# motor_driver_shield.net
KiCad netlist of a schematic drawn in EAGLE
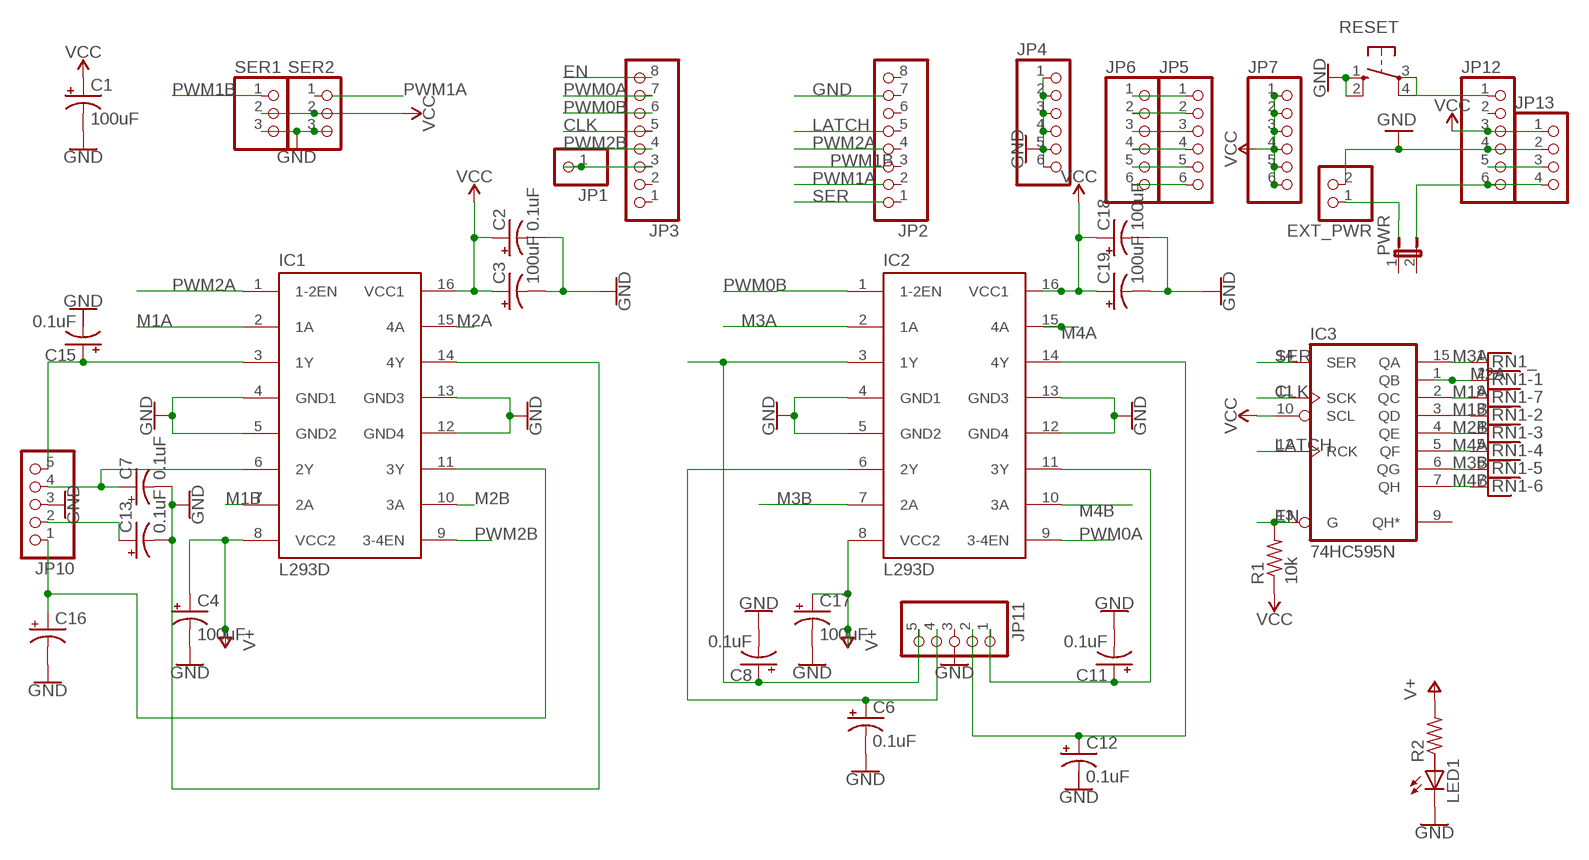
[diagram p0: schematic, sheet 1]

(export (version "E")
  (design (tool "Eeschema 10.0.6"))
  (components
    (comp (ref "C1")
      (value "100uF")
      (footprint "eagle-import:B45181A")
      (libsource (lib "eagle-import") (part "CPOL-USB45181A"))
    )
    (comp (ref "C2")
      (value "0.1uF")
      (footprint "eagle-import:B45181A")
      (libsource (lib "eagle-import") (part "CPOL-USB45181A"))
    )
    (comp (ref "C3")
      (value "100uF")
      (footprint "eagle-import:B45181A")
      (libsource (lib "eagle-import") (part "CPOL-USB45181A"))
    )
    (comp (ref "C4")
      (value "100uF")
      (footprint "eagle-import:B45181A")
      (libsource (lib "eagle-import") (part "CPOL-USB45181A"))
    )
    (comp (ref "C6")
      (value "0.1uF")
      (footprint "eagle-import:B45181A")
      (libsource (lib "eagle-import") (part "CPOL-USB45181A"))
    )
    (comp (ref "C7")
      (value "0.1uF")
      (footprint "eagle-import:B45181A")
      (libsource (lib "eagle-import") (part "CPOL-USB45181A"))
    )
    (comp (ref "C8")
      (value "0.1uF")
      (footprint "eagle-import:B45181A")
      (libsource (lib "eagle-import") (part "CPOL-USB45181A"))
    )
    (comp (ref "C11")
      (value "0.1uF")
      (footprint "eagle-import:B45181A")
      (libsource (lib "eagle-import") (part "CPOL-USB45181A"))
    )
    (comp (ref "C12")
      (value "0.1uF")
      (footprint "eagle-import:B45181A")
      (libsource (lib "eagle-import") (part "CPOL-USB45181A"))
    )
    (comp (ref "C13")
      (value "0.1uF")
      (footprint "eagle-import:B45181A")
      (libsource (lib "eagle-import") (part "CPOL-USB45181A"))
    )
    (comp (ref "C15")
      (value "0.1uF")
      (footprint "eagle-import:B45181A")
      (libsource (lib "eagle-import") (part "CPOL-USB45181A"))
    )
    (comp (ref "C16")
      (value "CPOL-USB45181A")
      (footprint "eagle-import:B45181A")
      (libsource (lib "eagle-import") (part "CPOL-USB45181A"))
    )
    (comp (ref "C17")
      (value "100uF")
      (footprint "eagle-import:B45181A")
      (libsource (lib "eagle-import") (part "CPOL-USB45181A"))
    )
    (comp (ref "C18")
      (value "100uF")
      (footprint "eagle-import:B45181A")
      (libsource (lib "eagle-import") (part "CPOL-USB45181A"))
    )
    (comp (ref "C19")
      (value "100uF")
      (footprint "eagle-import:B45181A")
      (libsource (lib "eagle-import") (part "CPOL-USB45181A"))
    )
    (comp (ref "EXT_PWR")
      (value "PINHD-1X2")
      (footprint "eagle-import:1X02")
      (libsource (lib "eagle-import") (part "PINHD-1X2"))
    )
    (comp (ref "IC1")
      (value "L293D")
      (footprint "eagle-import:DIL16")
      (libsource (lib "eagle-import") (part "L293D"))
    )
    (comp (ref "IC2")
      (value "L293D")
      (footprint "eagle-import:DIL16")
      (libsource (lib "eagle-import") (part "L293D"))
    )
    (comp (ref "IC3")
      (value "74HC595N")
      (footprint "eagle-import:DIL16")
      (libsource (lib "eagle-import") (part "74595NHC"))
    )
    (comp (ref "JP1")
      (value "PINHD-1X1")
      (footprint "eagle-import:1X01")
      (libsource (lib "eagle-import") (part "PINHD-1X1"))
    )
    (comp (ref "JP2")
      (value "PINHD-1X8-3.5MM")
      (footprint "eagle-import:1X08-3.5MM")
      (libsource (lib "eagle-import") (part "PINHD-1X8-3.5MM"))
    )
    (comp (ref "JP3")
      (value "PINHD-1X8-3.5MM")
      (footprint "eagle-import:1X08-3.5MM")
      (libsource (lib "eagle-import") (part "PINHD-1X8-3.5MM"))
    )
    (comp (ref "JP4")
      (value "PINHD-1X6-3.5MM")
      (footprint "eagle-import:1X06-3.5MM")
      (libsource (lib "eagle-import") (part "PINHD-1X6-3.5MM"))
    )
    (comp (ref "JP5")
      (value "PINHD-1X6-3.5MM")
      (footprint "eagle-import:1X06-3.5MM")
      (libsource (lib "eagle-import") (part "PINHD-1X6-3.5MM"))
    )
    (comp (ref "JP6")
      (value "PINHD-1X6-3.5MM")
      (footprint "eagle-import:1X06-3.5MM")
      (libsource (lib "eagle-import") (part "PINHD-1X6-3.5MM"))
    )
    (comp (ref "JP7")
      (value "PINHD-1X6-3.5MM")
      (footprint "eagle-import:1X06-3.5MM")
      (libsource (lib "eagle-import") (part "PINHD-1X6-3.5MM"))
    )
    (comp (ref "JP10")
      (value "PINHD-1X5")
      (footprint "eagle-import:1X05")
      (libsource (lib "eagle-import") (part "PINHD-1X5"))
    )
    (comp (ref "JP11")
      (value "PINHD-1X5")
      (footprint "eagle-import:1X05")
      (libsource (lib "eagle-import") (part "PINHD-1X5"))
    )
    (comp (ref "JP12")
      (value "PINHD-1X6-3.5MM")
      (footprint "eagle-import:1X06-3.5MM")
      (libsource (lib "eagle-import") (part "PINHD-1X6-3.5MM"))
    )
    (comp (ref "JP13")
      (value "PINHD-1X4")
      (footprint "eagle-import:1X04")
      (libsource (lib "eagle-import") (part "PINHD-1X4"))
    )
    (comp (ref "LED1")
      (value "LED5MM")
      (footprint "eagle-import:LED5MM")
      (libsource (lib "eagle-import") (part "LED5MM"))
    )
    (comp (ref "PWR")
      (value "JP1E")
      (footprint "eagle-import:JP1")
      (libsource (lib "eagle-import") (part "JP1E"))
    )
    (comp (ref "R1")
      (value "10k")
      (footprint "eagle-import:0204V")
      (libsource (lib "eagle-import") (part "R-US_0204/2V"))
    )
    (comp (ref "R2")
      (value "R-US_0204/2V")
      (footprint "eagle-import:0204V")
      (libsource (lib "eagle-import") (part "R-US_0204/2V"))
    )
    (comp (ref "RESET")
      (value "40-XX")
      (footprint "eagle-import:B3F-40XX")
      (fields (field (name "MF") "OMRON COMPONENTS USA") (field (name "MPN") "B3F-4000"))
      (libsource (lib "eagle-import") (part "40-XX"))
    )
    (comp (ref "RN1")
      (value "RNX7")
      (footprint "eagle-import:RN-8")
      (libsource (lib "eagle-import") (part "RNX7"))
    )
    (comp (ref "SER1")
      (value "PINHD-1X3")
      (footprint "eagle-import:1X03")
      (libsource (lib "eagle-import") (part "PINHD-1X3"))
    )
    (comp (ref "SER2")
      (value "PINHD-1X3")
      (footprint "eagle-import:1X03")
      (libsource (lib "eagle-import") (part "PINHD-1X3"))
    )
  )
  (nets
    (net (code "1") (name "/CLK") (class "Default")
      (node (ref "IC3") (pin "11") (pinfunction "SCK_11") (pintype "input"))
      (node (ref "JP3") (pin "5") (pinfunction "5_5") (pintype "passive"))
    )
    (net (code "2") (name "/EN") (class "Default")
      (node (ref "IC3") (pin "13") (pinfunction "G_13") (pintype "input"))
      (node (ref "JP3") (pin "8") (pinfunction "8_8") (pintype "passive"))
      (node (ref "R1") (pin "2") (pinfunction "2_2") (pintype "passive"))
    )
    (net (code "3") (name "/LATCH") (class "Default")
      (node (ref "IC3") (pin "12") (pinfunction "RCK_12") (pintype "input"))
    )
    (net (code "4") (name "/M1A") (class "Default")
      (node (ref "IC1") (pin "2") (pinfunction "1A_2") (pintype "input"))
      (node (ref "IC3") (pin "2") (pinfunction "QC_2") (pintype "tri_state"))
      (node (ref "RN1") (pin "8") (pinfunction "1_8") (pintype "passive"))
    )
    (net (code "5") (name "/M1B") (class "Default")
      (node (ref "IC1") (pin "7") (pinfunction "2A_7") (pintype "input"))
      (node (ref "IC3") (pin "3") (pinfunction "QD_3") (pintype "tri_state"))
      (node (ref "RN1") (pin "3") (pinfunction "1_3") (pintype "passive"))
    )
    (net (code "6") (name "/M2A") (class "Default")
      (node (ref "IC1") (pin "15") (pinfunction "4A_15") (pintype "input"))
      (node (ref "IC3") (pin "1") (pinfunction "QB_1") (pintype "tri_state"))
      (node (ref "RN1") (pin "2") (pinfunction "1_2") (pintype "passive"))
    )
    (net (code "7") (name "/M2B") (class "Default")
      (node (ref "IC1") (pin "10") (pinfunction "3A_10") (pintype "input"))
      (node (ref "IC3") (pin "4") (pinfunction "QE_4") (pintype "tri_state"))
      (node (ref "RN1") (pin "4") (pinfunction "1_4") (pintype "passive"))
    )
    (net (code "8") (name "/M3A") (class "Default")
      (node (ref "IC2") (pin "2") (pinfunction "1A_2") (pintype "input"))
      (node (ref "IC3") (pin "15") (pinfunction "QA_15") (pintype "tri_state"))
      (node (ref "RN1") (pin "1") (pinfunction "1_1") (pintype "passive"))
    )
    (net (code "9") (name "/M3B") (class "Default")
      (node (ref "IC2") (pin "7") (pinfunction "2A_7") (pintype "input"))
      (node (ref "IC3") (pin "6") (pinfunction "QG_6") (pintype "tri_state"))
      (node (ref "RN1") (pin "6") (pinfunction "1_6") (pintype "passive"))
    )
    (net (code "10") (name "/M4A") (class "Default")
      (node (ref "IC2") (pin "15") (pinfunction "4A_15") (pintype "input"))
      (node (ref "IC3") (pin "5") (pinfunction "QF_5") (pintype "tri_state"))
      (node (ref "RN1") (pin "5") (pinfunction "1_5") (pintype "passive"))
    )
    (net (code "11") (name "/M4B") (class "Default")
      (node (ref "IC2") (pin "10") (pinfunction "3A_10") (pintype "input"))
      (node (ref "IC3") (pin "7") (pinfunction "QH_7") (pintype "tri_state"))
      (node (ref "RN1") (pin "7") (pinfunction "1_7") (pintype "passive"))
    )
    (net (code "12") (name "/PWM0A") (class "Default")
      (node (ref "IC2") (pin "9") (pinfunction "3-4EN_9") (pintype "input"))
      (node (ref "JP3") (pin "7") (pinfunction "7_7") (pintype "passive"))
    )
    (net (code "13") (name "/PWM0B") (class "Default")
      (node (ref "IC2") (pin "1") (pinfunction "1-2EN_1") (pintype "input"))
      (node (ref "JP3") (pin "6") (pinfunction "6_6") (pintype "passive"))
    )
    (net (code "15") (name "/PWM1B") (class "Default")
      (node (ref "SER1") (pin "1") (pinfunction "1_1") (pintype "passive"))
    )
    (net (code "16") (name "/PWM2A") (class "Default")
      (node (ref "IC1") (pin "1") (pinfunction "1-2EN_1") (pintype "input"))
    )
    (net (code "17") (name "/PWM2B") (class "Default")
      (node (ref "IC1") (pin "9") (pinfunction "3-4EN_9") (pintype "input"))
      (node (ref "JP3") (pin "4") (pinfunction "4_4") (pintype "passive"))
    )
    (net (code "18") (name "/SER") (class "Default")
      (node (ref "IC3") (pin "14") (pinfunction "SER_14") (pintype "input"))
    )
    (net (code "19") (name "GND") (class "Default")
      (node (ref "C1") (pin "-") (pinfunction "-_-") (pintype "passive"))
      (node (ref "C11") (pin "-") (pinfunction "-_-") (pintype "passive"))
      (node (ref "C13") (pin "-") (pinfunction "-_-") (pintype "passive"))
      (node (ref "C16") (pin "-") (pinfunction "-_-") (pintype "passive"))
      (node (ref "C17") (pin "-") (pinfunction "-_-") (pintype "passive"))
      (node (ref "C18") (pin "-") (pinfunction "-_-") (pintype "passive"))
      (node (ref "C19") (pin "-") (pinfunction "-_-") (pintype "passive"))
      (node (ref "C2") (pin "-") (pinfunction "-_-") (pintype "passive"))
      (node (ref "C3") (pin "-") (pinfunction "-_-") (pintype "passive"))
      (node (ref "C4") (pin "-") (pinfunction "-_-") (pintype "passive"))
      (node (ref "C6") (pin "-") (pinfunction "-_-") (pintype "passive"))
      (node (ref "C7") (pin "-") (pinfunction "-_-") (pintype "passive"))
      (node (ref "C8") (pin "-") (pinfunction "-_-") (pintype "passive"))
      (node (ref "EXT_PWR") (pin "2") (pinfunction "2_2") (pintype "passive"))
      (node (ref "IC1") (pin "12") (pinfunction "GND4_12") (pintype "power_in"))
      (node (ref "IC1") (pin "13") (pinfunction "GND3_13") (pintype "power_in"))
      (node (ref "IC1") (pin "14") (pinfunction "4Y_14") (pintype "output"))
      (node (ref "IC1") (pin "4") (pinfunction "GND1_4") (pintype "power_in"))
      (node (ref "IC1") (pin "5") (pinfunction "GND2_5") (pintype "power_in"))
      (node (ref "IC2") (pin "12") (pinfunction "GND4_12") (pintype "power_in"))
      (node (ref "IC2") (pin "13") (pinfunction "GND3_13") (pintype "power_in"))
      (node (ref "IC2") (pin "4") (pinfunction "GND1_4") (pintype "power_in"))
      (node (ref "IC2") (pin "5") (pinfunction "GND2_5") (pintype "power_in"))
      (node (ref "JP10") (pin "3") (pinfunction "3_3") (pintype "passive"))
      (node (ref "JP12") (pin "4") (pinfunction "4_4") (pintype "passive"))
      (node (ref "JP13") (pin "2") (pinfunction "2_2") (pintype "passive"))
      (node (ref "JP4") (pin "1") (pinfunction "1_1") (pintype "passive"))
      (node (ref "JP4") (pin "2") (pinfunction "2_2") (pintype "passive"))
      (node (ref "JP4") (pin "3") (pinfunction "3_3") (pintype "passive"))
      (node (ref "JP4") (pin "4") (pinfunction "4_4") (pintype "passive"))
      (node (ref "JP4") (pin "5") (pinfunction "5_5") (pintype "passive"))
      (node (ref "JP4") (pin "6") (pinfunction "6_6") (pintype "passive"))
      (node (ref "LED1") (pin "K") (pinfunction "C_K") (pintype "passive"))
      (node (ref "RESET") (pin "1") (pinfunction "S_1") (pintype "passive"))
      (node (ref "RESET") (pin "2") (pinfunction "S1_2") (pintype "passive"))
      (node (ref "SER1") (pin "3") (pinfunction "3_3") (pintype "passive"))
      (node (ref "SER2") (pin "3") (pinfunction "3_3") (pintype "passive"))
    )
    (net (code "20") (name "Net-(C13-Pad+)") (class "Default")
      (node (ref "C13") (pin "+") (pinfunction "+_+") (pintype "passive"))
      (node (ref "JP10") (pin "2") (pinfunction "2_2") (pintype "passive"))
    )
    (net (code "21") (name "Net-(IC1-1Y)") (class "Default")
      (node (ref "C15") (pin "+") (pinfunction "+_+") (pintype "passive"))
      (node (ref "IC1") (pin "3") (pinfunction "1Y_3") (pintype "output"))
      (node (ref "JP10") (pin "5") (pinfunction "5_5") (pintype "passive"))
    )
    (net (code "22") (name "Net-(IC1-2Y)") (class "Default")
      (node (ref "C7") (pin "+") (pinfunction "+_+") (pintype "passive"))
      (node (ref "IC1") (pin "6") (pinfunction "2Y_6") (pintype "output"))
      (node (ref "JP10") (pin "4") (pinfunction "4_4") (pintype "passive"))
    )
    (net (code "23") (name "Net-(IC1-3Y)") (class "Default")
      (node (ref "C16") (pin "+") (pinfunction "+_+") (pintype "passive"))
      (node (ref "IC1") (pin "11") (pinfunction "3Y_11") (pintype "output"))
      (node (ref "JP10") (pin "1") (pinfunction "1_1") (pintype "passive"))
    )
    (net (code "24") (name "Net-(IC2-1Y)") (class "Default")
      (node (ref "C8") (pin "+") (pinfunction "+_+") (pintype "passive"))
      (node (ref "IC2") (pin "3") (pinfunction "1Y_3") (pintype "output"))
      (node (ref "JP11") (pin "5") (pinfunction "5_5") (pintype "passive"))
    )
    (net (code "25") (name "Net-(IC2-2Y)") (class "Default")
      (node (ref "C6") (pin "+") (pinfunction "+_+") (pintype "passive"))
      (node (ref "IC2") (pin "6") (pinfunction "2Y_6") (pintype "output"))
      (node (ref "JP11") (pin "4") (pinfunction "4_4") (pintype "passive"))
    )
    (net (code "26") (name "Net-(IC2-3Y)") (class "Default")
      (node (ref "C11") (pin "+") (pinfunction "+_+") (pintype "passive"))
      (node (ref "IC2") (pin "11") (pinfunction "3Y_11") (pintype "output"))
      (node (ref "JP11") (pin "1") (pinfunction "1_1") (pintype "passive"))
    )
    (net (code "27") (name "Net-(IC2-4Y)") (class "Default")
      (node (ref "C12") (pin "+") (pinfunction "+_+") (pintype "passive"))
      (node (ref "IC2") (pin "14") (pinfunction "4Y_14") (pintype "output"))
      (node (ref "JP11") (pin "2") (pinfunction "2_2") (pintype "passive"))
    )
    (net (code "28") (name "Net-(JP1-Pad1)") (class "Default")
      (node (ref "JP1") (pin "1") (pinfunction "1_1") (pintype "passive"))
      (node (ref "JP3") (pin "3") (pinfunction "3_3") (pintype "passive"))
    )
    (net (code "29") (name "Net-(JP5-Pad1)") (class "Default")
      (node (ref "JP5") (pin "1") (pinfunction "1_1") (pintype "passive"))
      (node (ref "JP6") (pin "1") (pinfunction "1_1") (pintype "passive"))
    )
    (net (code "30") (name "Net-(JP5-Pad2)") (class "Default")
      (node (ref "JP5") (pin "2") (pinfunction "2_2") (pintype "passive"))
      (node (ref "JP6") (pin "2") (pinfunction "2_2") (pintype "passive"))
    )
    (net (code "31") (name "Net-(JP5-Pad3)") (class "Default")
      (node (ref "JP5") (pin "3") (pinfunction "3_3") (pintype "passive"))
      (node (ref "JP6") (pin "3") (pinfunction "3_3") (pintype "passive"))
    )
    (net (code "32") (name "Net-(JP5-Pad4)") (class "Default")
      (node (ref "JP5") (pin "4") (pinfunction "4_4") (pintype "passive"))
      (node (ref "JP6") (pin "4") (pinfunction "4_4") (pintype "passive"))
    )
    (net (code "33") (name "Net-(JP5-Pad5)") (class "Default")
      (node (ref "JP5") (pin "5") (pinfunction "5_5") (pintype "passive"))
      (node (ref "JP6") (pin "5") (pinfunction "5_5") (pintype "passive"))
    )
    (net (code "34") (name "Net-(JP5-Pad6)") (class "Default")
      (node (ref "JP5") (pin "6") (pinfunction "6_6") (pintype "passive"))
      (node (ref "JP6") (pin "6") (pinfunction "6_6") (pintype "passive"))
    )
    (net (code "35") (name "Net-(JP12-Pad5)") (class "Default")
      (node (ref "JP12") (pin "5") (pinfunction "5_5") (pintype "passive"))
      (node (ref "JP13") (pin "3") (pinfunction "3_3") (pintype "passive"))
    )
    (net (code "36") (name "Net-(JP12-Pad6)") (class "Default")
      (node (ref "JP12") (pin "6") (pinfunction "6_6") (pintype "passive"))
      (node (ref "JP13") (pin "4") (pinfunction "4_4") (pintype "passive"))
    )
    (net (code "37") (name "Net-(RESET-P)") (class "Default")
      (node (ref "JP12") (pin "1") (pinfunction "1_1") (pintype "passive"))
      (node (ref "RESET") (pin "3") (pinfunction "P_3") (pintype "passive"))
      (node (ref "RESET") (pin "4") (pinfunction "P1_4") (pintype "passive"))
    )
    (net (code "38") (name "V+") (class "Default")
      (node (ref "C17") (pin "+") (pinfunction "+_+") (pintype "passive"))
      (node (ref "C4") (pin "+") (pinfunction "+_+") (pintype "passive"))
      (node (ref "IC1") (pin "8") (pinfunction "VCC2_8") (pintype "power_in"))
      (node (ref "IC2") (pin "8") (pinfunction "VCC2_8") (pintype "power_in"))
      (node (ref "R2") (pin "2") (pinfunction "2_2") (pintype "passive"))
    )
    (net (code "39") (name "VCC") (class "Default")
      (node (ref "C1") (pin "+") (pinfunction "+_+") (pintype "passive"))
      (node (ref "C18") (pin "+") (pinfunction "+_+") (pintype "passive"))
      (node (ref "C19") (pin "+") (pinfunction "+_+") (pintype "passive"))
      (node (ref "C2") (pin "+") (pinfunction "+_+") (pintype "passive"))
      (node (ref "C3") (pin "+") (pinfunction "+_+") (pintype "passive"))
      (node (ref "IC1") (pin "16") (pinfunction "VCC1_16") (pintype "power_in"))
      (node (ref "IC2") (pin "16") (pinfunction "VCC1_16") (pintype "power_in"))
      (node (ref "IC3") (pin "10") (pinfunction "SCL_10") (pintype "input"))
      (node (ref "JP12") (pin "3") (pinfunction "3_3") (pintype "passive"))
      (node (ref "JP13") (pin "1") (pinfunction "1_1") (pintype "passive"))
      (node (ref "JP7") (pin "1") (pinfunction "1_1") (pintype "passive"))
      (node (ref "JP7") (pin "2") (pinfunction "2_2") (pintype "passive"))
      (node (ref "JP7") (pin "3") (pinfunction "3_3") (pintype "passive"))
      (node (ref "JP7") (pin "4") (pinfunction "4_4") (pintype "passive"))
      (node (ref "JP7") (pin "5") (pinfunction "5_5") (pintype "passive"))
      (node (ref "JP7") (pin "6") (pinfunction "6_6") (pintype "passive"))
      (node (ref "R1") (pin "1") (pinfunction "1_1") (pintype "passive"))
      (node (ref "SER1") (pin "2") (pinfunction "2_2") (pintype "passive"))
      (node (ref "SER2") (pin "2") (pinfunction "2_2") (pintype "passive"))
    )
    (net (code "40") (name "unconnected-(C12-Pad-)") (class "Default")
      (node (ref "C12") (pin "-") (pinfunction "-_-") (pintype "passive"))
    )
    (net (code "41") (name "unconnected-(C15-Pad-)") (class "Default")
      (node (ref "C15") (pin "-") (pinfunction "-_-") (pintype "passive"))
    )
    (net (code "42") (name "unconnected-(EXT_PWR-Pad1)") (class "Default")
      (node (ref "EXT_PWR") (pin "1") (pinfunction "1_1") (pintype "passive"))
    )
    (net (code "43") (name "unconnected-(IC3A-QH*-Pad9)") (class "Default")
      (node (ref "IC3") (pin "9") (pinfunction "QH*_9") (pintype "tri_state"))
    )
    (net (code "44") (name "unconnected-(JP2-Pad1)") (class "Default")
      (node (ref "JP2") (pin "1") (pinfunction "1_1") (pintype "passive"))
    )
    (net (code "45") (name "unconnected-(JP2-Pad2)") (class "Default")
      (node (ref "JP2") (pin "2") (pinfunction "2_2") (pintype "passive"))
    )
    (net (code "46") (name "unconnected-(JP2-Pad3)") (class "Default")
      (node (ref "JP2") (pin "3") (pinfunction "3_3") (pintype "passive"))
    )
    (net (code "47") (name "unconnected-(JP2-Pad4)") (class "Default")
      (node (ref "JP2") (pin "4") (pinfunction "4_4") (pintype "passive"))
    )
    (net (code "48") (name "unconnected-(JP2-Pad5)") (class "Default")
      (node (ref "JP2") (pin "5") (pinfunction "5_5") (pintype "passive"))
    )
    (net (code "49") (name "unconnected-(JP2-Pad6)") (class "Default")
      (node (ref "JP2") (pin "6") (pinfunction "6_6") (pintype "passive"))
    )
    (net (code "50") (name "unconnected-(JP2-Pad7)") (class "Default")
      (node (ref "JP2") (pin "7") (pinfunction "7_7") (pintype "passive"))
    )
    (net (code "51") (name "unconnected-(JP2-Pad8)") (class "Default")
      (node (ref "JP2") (pin "8") (pinfunction "8_8") (pintype "passive"))
    )
    (net (code "52") (name "unconnected-(JP3-Pad1)") (class "Default")
      (node (ref "JP3") (pin "1") (pinfunction "1_1") (pintype "passive"))
    )
    (net (code "53") (name "unconnected-(JP3-Pad2)") (class "Default")
      (node (ref "JP3") (pin "2") (pinfunction "2_2") (pintype "passive"))
    )
    (net (code "54") (name "unconnected-(JP11-Pad3)") (class "Default")
      (node (ref "JP11") (pin "3") (pinfunction "3_3") (pintype "passive"))
    )
    (net (code "55") (name "unconnected-(JP12-Pad2)") (class "Default")
      (node (ref "JP12") (pin "2") (pinfunction "2_2") (pintype "passive"))
    )
    (net (code "56") (name "unconnected-(LED1-PadA)") (class "Default")
      (node (ref "LED1") (pin "A") (pinfunction "A_A") (pintype "passive"))
    )
    (net (code "57") (name "unconnected-(PWR-Pad1)") (class "Default")
      (node (ref "PWR") (pin "1") (pinfunction "1_1") (pintype "passive"))
    )
    (net (code "58") (name "unconnected-(PWR-Pad2)") (class "Default")
      (node (ref "PWR") (pin "2") (pinfunction "2_2") (pintype "passive"))
    )
    (net (code "59") (name "unconnected-(R2-Pad1)") (class "Default")
      (node (ref "R2") (pin "1") (pinfunction "1_1") (pintype "passive"))
    )
    (net (code "60") (name "unconnected-(SER2-Pad1)") (class "Default")
      (node (ref "SER2") (pin "1") (pinfunction "1_1") (pintype "passive"))
    )
  )
)
